# Resolver.net
KiCad netlist of a schematic drawn in Altium Designer
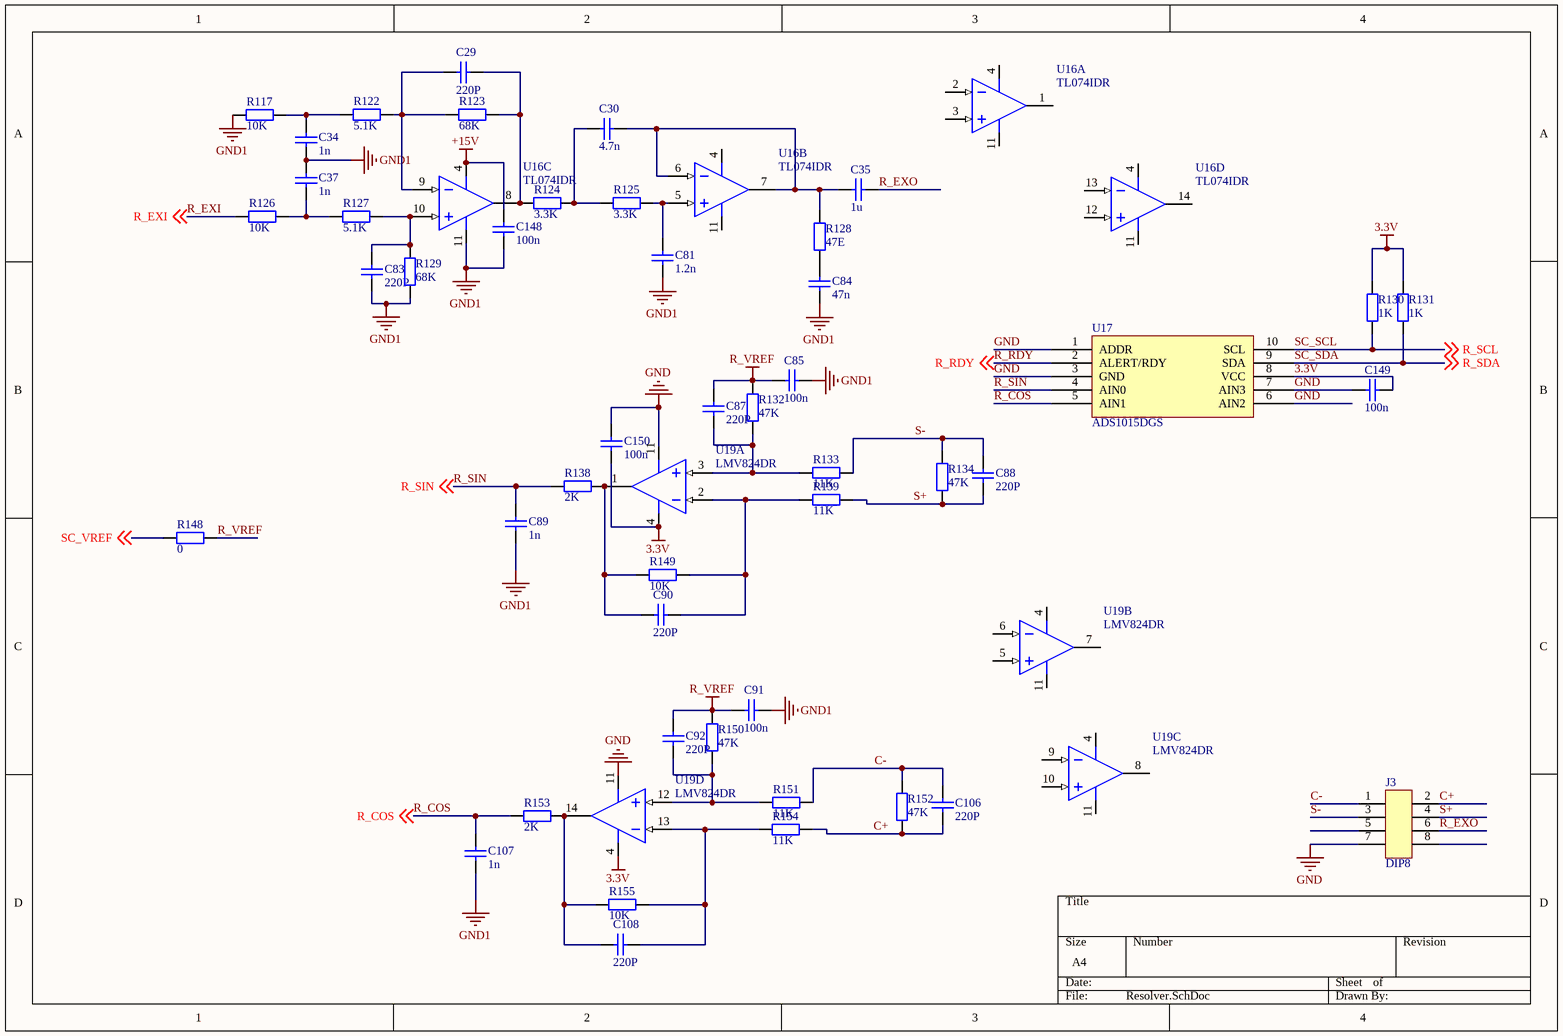
[diagram p0: Resolver.SchDoc]

(export (version "E")
  (design (tool "Eeschema 10.0.6"))
  (components
    (comp (ref "C29")
      (value "220P")
      (footprint "0603C")
      (description "Capacitor")
      (fields (field (name "PUBLISHER") "Altium Limited"))
      (libsource (lib "Main_C") (part "Cap"))
    )
    (comp (ref "C30")
      (value "4.7n")
      (footprint "0603C")
      (description "Capacitor")
      (fields (field (name "PUBLISHER") "Altium Limited"))
      (libsource (lib "Main_C") (part "Cap"))
    )
    (comp (ref "C34")
      (value "1n")
      (footprint "0603C")
      (description "Capacitor")
      (fields (field (name "PUBLISHER") "Altium Limited"))
      (libsource (lib "Main_C") (part "Cap"))
    )
    (comp (ref "C35")
      (value "1u")
      (footprint "0603C")
      (description "Capacitor")
      (fields (field (name "PUBLISHER") "Altium Limited"))
      (libsource (lib "Main_C") (part "Cap"))
    )
    (comp (ref "C37")
      (value "1n")
      (footprint "0603C")
      (description "Capacitor")
      (fields (field (name "PUBLISHER") "Altium Limited"))
      (libsource (lib "Main_C") (part "Cap"))
    )
    (comp (ref "C81")
      (value "1.2n")
      (footprint "0603C")
      (description "Capacitor")
      (fields (field (name "PUBLISHER") "Altium Limited"))
      (libsource (lib "Main_C") (part "Cap"))
    )
    (comp (ref "C83")
      (value "220P")
      (footprint "0603C")
      (description "Capacitor")
      (fields (field (name "PUBLISHER") "Altium Limited"))
      (libsource (lib "Main_C") (part "Cap"))
    )
    (comp (ref "C84")
      (value "47n")
      (footprint "0603C")
      (description "Capacitor")
      (fields (field (name "PUBLISHER") "Altium Limited"))
      (libsource (lib "Main_C") (part "Cap"))
    )
    (comp (ref "C85")
      (value "100n")
      (footprint "0603C")
      (description "Capacitor")
      (fields (field (name "PUBLISHER") "Altium Limited"))
      (libsource (lib "Main_C") (part "Cap"))
    )
    (comp (ref "C87")
      (value "220P")
      (footprint "0603C")
      (description "Capacitor")
      (fields (field (name "PUBLISHER") "Altium Limited"))
      (libsource (lib "Main_C") (part "Cap"))
    )
    (comp (ref "C88")
      (value "220P")
      (footprint "0603C")
      (description "Capacitor")
      (fields (field (name "PUBLISHER") "Altium Limited"))
      (libsource (lib "Main_C") (part "Cap"))
    )
    (comp (ref "C89")
      (value "1n")
      (footprint "0603C")
      (description "Capacitor")
      (fields (field (name "PUBLISHER") "Altium Limited"))
      (libsource (lib "Main_C") (part "Cap"))
    )
    (comp (ref "C90")
      (value "220P")
      (footprint "0603C")
      (description "Capacitor")
      (fields (field (name "PUBLISHER") "Altium Limited"))
      (libsource (lib "Main_C") (part "Cap"))
    )
    (comp (ref "C91")
      (value "100n")
      (footprint "0603C")
      (description "Capacitor")
      (fields (field (name "PUBLISHER") "Altium Limited"))
      (libsource (lib "Main_C") (part "Cap"))
    )
    (comp (ref "C92")
      (value "220P")
      (footprint "0603C")
      (description "Capacitor")
      (fields (field (name "PUBLISHER") "Altium Limited"))
      (libsource (lib "Main_C") (part "Cap"))
    )
    (comp (ref "C106")
      (value "220P")
      (footprint "0603C")
      (description "Capacitor")
      (fields (field (name "PUBLISHER") "Altium Limited"))
      (libsource (lib "Main_C") (part "Cap"))
    )
    (comp (ref "C107")
      (value "1n")
      (footprint "0603C")
      (description "Capacitor")
      (fields (field (name "PUBLISHER") "Altium Limited"))
      (libsource (lib "Main_C") (part "Cap"))
    )
    (comp (ref "C108")
      (value "220P")
      (footprint "0603C")
      (description "Capacitor")
      (fields (field (name "PUBLISHER") "Altium Limited"))
      (libsource (lib "Main_C") (part "Cap"))
    )
    (comp (ref "C148")
      (value "100n")
      (footprint "0603C")
      (description "Capacitor")
      (fields (field (name "PUBLISHER") "Altium Limited"))
      (libsource (lib "Main_C") (part "Cap"))
    )
    (comp (ref "C149")
      (value "100n")
      (footprint "0603C")
      (description "Capacitor")
      (fields (field (name "PUBLISHER") "Altium Limited"))
      (libsource (lib "Main_C") (part "Cap"))
    )
    (comp (ref "C150")
      (value "100n")
      (footprint "0603C")
      (description "Capacitor")
      (fields (field (name "PUBLISHER") "Altium Limited"))
      (libsource (lib "Main_C") (part "Cap"))
    )
    (comp (ref "J3")
      (value "DIP8")
      (footprint "DIP8-2.54")
      (description "Connectors")
      (fields (field (name "PUBLISHER") "Altium Limited"))
      (libsource (lib "jointbar") (part "DIP8"))
    )
    (comp (ref "R117")
      (value "10K")
      (footprint "0603R")
      (description "Resistor")
      (fields (field (name "PUBLISHER") "Altium Limited"))
      (libsource (lib "") (part "Res2_1"))
    )
    (comp (ref "R122")
      (value "5.1K")
      (footprint "0603R")
      (description "Resistor")
      (fields (field (name "PUBLISHER") "Altium Limited"))
      (libsource (lib "") (part "Res2_1"))
    )
    (comp (ref "R123")
      (value "68K")
      (footprint "0603R")
      (description "Resistor")
      (fields (field (name "PUBLISHER") "Altium Limited"))
      (libsource (lib "") (part "Res2_1"))
    )
    (comp (ref "R124")
      (value "3.3K")
      (footprint "0603R")
      (description "Resistor")
      (fields (field (name "PUBLISHER") "Altium Limited"))
      (libsource (lib "") (part "Res2_1"))
    )
    (comp (ref "R125")
      (value "3.3K")
      (footprint "0603R")
      (description "Resistor")
      (fields (field (name "PUBLISHER") "Altium Limited"))
      (libsource (lib "") (part "Res2_1"))
    )
    (comp (ref "R126")
      (value "10K")
      (footprint "0603R")
      (description "Resistor")
      (fields (field (name "PUBLISHER") "Altium Limited"))
      (libsource (lib "") (part "Res2_1"))
    )
    (comp (ref "R127")
      (value "5.1K")
      (footprint "0603R")
      (description "Resistor")
      (fields (field (name "PUBLISHER") "Altium Limited"))
      (libsource (lib "") (part "Res2_1"))
    )
    (comp (ref "R128")
      (value "47E")
      (footprint "0603R")
      (description "Resistor")
      (fields (field (name "PUBLISHER") "Altium Limited"))
      (libsource (lib "Main_C") (part "Res2"))
    )
    (comp (ref "R129")
      (value "68K")
      (footprint "0603R")
      (description "Resistor")
      (fields (field (name "PUBLISHER") "Altium Limited"))
      (libsource (lib "Main_C") (part "Res2"))
    )
    (comp (ref "R130")
      (value "1K")
      (footprint "0603R")
      (description "Resistor")
      (fields (field (name "PUBLISHER") "Altium Limited"))
      (libsource (lib "Main_C") (part "Res2"))
    )
    (comp (ref "R131")
      (value "1K")
      (footprint "0603R")
      (description "Resistor")
      (fields (field (name "PUBLISHER") "Altium Limited"))
      (libsource (lib "Main_C") (part "Res2"))
    )
    (comp (ref "R132")
      (value "47K")
      (footprint "0603R")
      (description "Resistor")
      (fields (field (name "PUBLISHER") "Altium Limited"))
      (libsource (lib "Main_C") (part "Res2"))
    )
    (comp (ref "R133")
      (value "11K")
      (footprint "0603R")
      (description "Resistor")
      (fields (field (name "PUBLISHER") "Altium Limited"))
      (libsource (lib "") (part "Res2_1"))
    )
    (comp (ref "R134")
      (value "47K")
      (footprint "0603R")
      (description "Resistor")
      (fields (field (name "PUBLISHER") "Altium Limited"))
      (libsource (lib "Main_C") (part "Res2"))
    )
    (comp (ref "R138")
      (value "2K")
      (footprint "0603R")
      (description "Resistor")
      (fields (field (name "PUBLISHER") "Altium Limited"))
      (libsource (lib "") (part "Res2_2"))
    )
    (comp (ref "R139")
      (value "11K")
      (footprint "0603R")
      (description "Resistor")
      (fields (field (name "PUBLISHER") "Altium Limited"))
      (libsource (lib "") (part "Res2_1"))
    )
    (comp (ref "R148")
      (value "0")
      (footprint "0603R")
      (description "Resistor")
      (fields (field (name "PUBLISHER") "Altium Limited"))
      (libsource (lib "") (part "Res2_1"))
    )
    (comp (ref "R149")
      (value "10K")
      (footprint "0603R")
      (description "Resistor")
      (fields (field (name "PUBLISHER") "Altium Limited"))
      (libsource (lib "") (part "Res2_2"))
    )
    (comp (ref "R150")
      (value "47K")
      (footprint "0603R")
      (description "Resistor")
      (fields (field (name "PUBLISHER") "Altium Limited"))
      (libsource (lib "Main_C") (part "Res2"))
    )
    (comp (ref "R151")
      (value "11K")
      (footprint "0603R")
      (description "Resistor")
      (fields (field (name "PUBLISHER") "Altium Limited"))
      (libsource (lib "") (part "Res2_1"))
    )
    (comp (ref "R152")
      (value "47K")
      (footprint "0603R")
      (description "Resistor")
      (fields (field (name "PUBLISHER") "Altium Limited"))
      (libsource (lib "Main_C") (part "Res2"))
    )
    (comp (ref "R153")
      (value "2K")
      (footprint "0603R")
      (description "Resistor")
      (fields (field (name "PUBLISHER") "Altium Limited"))
      (libsource (lib "") (part "Res2_2"))
    )
    (comp (ref "R154")
      (value "11K")
      (footprint "0603R")
      (description "Resistor")
      (fields (field (name "PUBLISHER") "Altium Limited"))
      (libsource (lib "") (part "Res2_1"))
    )
    (comp (ref "R155")
      (value "10K")
      (footprint "0603R")
      (description "Resistor")
      (fields (field (name "PUBLISHER") "Altium Limited"))
      (libsource (lib "") (part "Res2_2"))
    )
    (comp (ref "U16")
      (value "TL074IDR")
      (footprint "SOP-14")
      (description "Quad Single-Supply Comparator")
      (fields (field (name "PUBLISHER") "Altium Limited"))
      (libsource (lib "Main_C") (part "LM339AD"))
    )
    (comp (ref "U17") (value "ADS1015DGS") (footprint "VSSOP-10") (libsource (lib "Main_C") (part "ADS1015")))
    (comp (ref "U19")
      (value "LMV824DR")
      (footprint "SOP-14")
      (description "Quad Single-Supply Comparator")
      (fields (field (name "PUBLISHER") "Altium Limited"))
      (libsource (lib "Main_C") (part "LM339AD"))
    )
  )
  (nets
    (net (code "1") (name "+15V") (class "Default")
      (node (ref "C148") (pin "2") (pinfunction "2_2") (pintype "passive"))
      (node (ref "U16") (pin "4") (pinfunction "GND_4") (pintype "power_in"))
    )
    (net (code "2") (name "/C+") (class "Default")
      (node (ref "C106") (pin "2") (pinfunction "2_2") (pintype "passive"))
      (node (ref "J3") (pin "2") (pinfunction "2_2") (pintype "passive"))
      (node (ref "R152") (pin "2") (pinfunction "2_2") (pintype "passive"))
      (node (ref "R154") (pin "1") (pinfunction "1_1") (pintype "passive"))
    )
    (net (code "3") (name "/C-") (class "Default")
      (node (ref "C106") (pin "1") (pinfunction "1_1") (pintype "passive"))
      (node (ref "J3") (pin "1") (pinfunction "1_1") (pintype "passive"))
      (node (ref "R151") (pin "1") (pinfunction "1_1") (pintype "passive"))
      (node (ref "R152") (pin "1") (pinfunction "1_1") (pintype "passive"))
    )
    (net (code "4") (name "/R_EXO") (class "Default")
      (node (ref "C35") (pin "2") (pinfunction "2_2") (pintype "passive"))
      (node (ref "J3") (pin "6") (pinfunction "6_6") (pintype "passive"))
    )
    (net (code "5") (name "/S+") (class "Default")
      (node (ref "C88") (pin "2") (pinfunction "2_2") (pintype "passive"))
      (node (ref "J3") (pin "4") (pinfunction "4_4") (pintype "passive"))
      (node (ref "R134") (pin "2") (pinfunction "2_2") (pintype "passive"))
      (node (ref "R139") (pin "1") (pinfunction "1_1") (pintype "passive"))
    )
    (net (code "6") (name "/S-") (class "Default")
      (node (ref "C88") (pin "1") (pinfunction "1_1") (pintype "passive"))
      (node (ref "J3") (pin "3") (pinfunction "3_3") (pintype "passive"))
      (node (ref "R133") (pin "1") (pinfunction "1_1") (pintype "passive"))
      (node (ref "R134") (pin "1") (pinfunction "1_1") (pintype "passive"))
    )
    (net (code "7") (name "3.3V") (class "Default")
      (node (ref "C149") (pin "2") (pinfunction "2_2") (pintype "passive"))
      (node (ref "C150") (pin "1") (pinfunction "1_1") (pintype "passive"))
      (node (ref "R130") (pin "1") (pinfunction "1_1") (pintype "passive"))
      (node (ref "R131") (pin "1") (pinfunction "1_1") (pintype "passive"))
      (node (ref "U17") (pin "8") (pinfunction "VCC_8") (pintype "passive"))
      (node (ref "U19") (pin "4") (pinfunction "GND_4") (pintype "power_in"))
    )
    (net (code "8") (name "GND") (class "Default")
      (node (ref "C149") (pin "1") (pinfunction "1_1") (pintype "passive"))
      (node (ref "C150") (pin "2") (pinfunction "2_2") (pintype "passive"))
      (node (ref "J3") (pin "7") (pinfunction "7_7") (pintype "passive"))
      (node (ref "U17") (pin "1") (pinfunction "ADDR_1") (pintype "passive"))
      (node (ref "U17") (pin "3") (pinfunction "GND_3") (pintype "passive"))
      (node (ref "U17") (pin "6") (pinfunction "AIN2_6") (pintype "passive"))
      (node (ref "U17") (pin "7") (pinfunction "AIN3_7") (pintype "passive"))
      (node (ref "U19") (pin "11") (pinfunction "V+_11") (pintype "power_in"))
    )
    (net (code "9") (name "GND1") (class "Default")
      (node (ref "C107") (pin "1") (pinfunction "1_1") (pintype "passive"))
      (node (ref "C148") (pin "1") (pinfunction "1_1") (pintype "passive"))
      (node (ref "C34") (pin "1") (pinfunction "1_1") (pintype "passive"))
      (node (ref "C37") (pin "2") (pinfunction "2_2") (pintype "passive"))
      (node (ref "C81") (pin "1") (pinfunction "1_1") (pintype "passive"))
      (node (ref "C83") (pin "1") (pinfunction "1_1") (pintype "passive"))
      (node (ref "C84") (pin "1") (pinfunction "1_1") (pintype "passive"))
      (node (ref "C85") (pin "1") (pinfunction "1_1") (pintype "passive"))
      (node (ref "C89") (pin "1") (pinfunction "1_1") (pintype "passive"))
      (node (ref "C91") (pin "1") (pinfunction "1_1") (pintype "passive"))
      (node (ref "R117") (pin "2") (pinfunction "2_2") (pintype "passive"))
      (node (ref "R129") (pin "2") (pinfunction "2_2") (pintype "passive"))
      (node (ref "U16") (pin "11") (pinfunction "V+_11") (pintype "power_in"))
    )
    (net (code "10") (name "Net-(C30-Pad1)") (class "Default")
      (node (ref "C30") (pin "1") (pinfunction "1_1") (pintype "passive"))
      (node (ref "R124") (pin "1") (pinfunction "1_1") (pintype "passive"))
      (node (ref "R125") (pin "2") (pinfunction "2_2") (pintype "passive"))
    )
    (net (code "11") (name "Net-(C34-Pad2)") (class "Default")
      (node (ref "C34") (pin "2") (pinfunction "2_2") (pintype "passive"))
      (node (ref "R117") (pin "1") (pinfunction "1_1") (pintype "passive"))
      (node (ref "R122") (pin "2") (pinfunction "2_2") (pintype "passive"))
    )
    (net (code "12") (name "Net-(C37-Pad1)") (class "Default")
      (node (ref "C37") (pin "1") (pinfunction "1_1") (pintype "passive"))
      (node (ref "R126") (pin "1") (pinfunction "1_1") (pintype "passive"))
      (node (ref "R127") (pin "2") (pinfunction "2_2") (pintype "passive"))
    )
    (net (code "13") (name "Net-(C84-Pad2)") (class "Default")
      (node (ref "C84") (pin "2") (pinfunction "2_2") (pintype "passive"))
      (node (ref "R128") (pin "2") (pinfunction "2_2") (pintype "passive"))
    )
    (net (code "14") (name "Net-(U16B-IN+)") (class "Default")
      (node (ref "C81") (pin "2") (pinfunction "2_2") (pintype "passive"))
      (node (ref "R125") (pin "1") (pinfunction "1_1") (pintype "passive"))
      (node (ref "U16") (pin "5") (pinfunction "IN+_5") (pintype "input"))
    )
    (net (code "15") (name "Net-(U16B-IN-)") (class "Default")
      (node (ref "C30") (pin "2") (pinfunction "2_2") (pintype "passive"))
      (node (ref "C35") (pin "1") (pinfunction "1_1") (pintype "passive"))
      (node (ref "R128") (pin "1") (pinfunction "1_1") (pintype "passive"))
      (node (ref "U16") (pin "6") (pinfunction "IN-_6") (pintype "input"))
      (node (ref "U16") (pin "7") (pinfunction "OUT2_7") (pintype "open_collector"))
    )
    (net (code "16") (name "Net-(U16C-IN+)") (class "Default")
      (node (ref "C83") (pin "2") (pinfunction "2_2") (pintype "passive"))
      (node (ref "R127") (pin "1") (pinfunction "1_1") (pintype "passive"))
      (node (ref "R129") (pin "1") (pinfunction "1_1") (pintype "passive"))
      (node (ref "U16") (pin "10") (pinfunction "IN+_10") (pintype "input"))
    )
    (net (code "17") (name "Net-(U16C-IN-)") (class "Default")
      (node (ref "C29") (pin "1") (pinfunction "1_1") (pintype "passive"))
      (node (ref "R122") (pin "1") (pinfunction "1_1") (pintype "passive"))
      (node (ref "R123") (pin "2") (pinfunction "2_2") (pintype "passive"))
      (node (ref "U16") (pin "9") (pinfunction "IN-_9") (pintype "input"))
    )
    (net (code "18") (name "Net-(U16C-OUT)") (class "Default")
      (node (ref "C29") (pin "2") (pinfunction "2_2") (pintype "passive"))
      (node (ref "R123") (pin "1") (pinfunction "1_1") (pintype "passive"))
      (node (ref "R124") (pin "2") (pinfunction "2_2") (pintype "passive"))
      (node (ref "U16") (pin "8") (pinfunction "OUT_8") (pintype "open_collector"))
    )
    (net (code "19") (name "Net-(U19A-IN+)") (class "Default")
      (node (ref "C87") (pin "1") (pinfunction "1_1") (pintype "passive"))
      (node (ref "R132") (pin "2") (pinfunction "2_2") (pintype "passive"))
      (node (ref "R133") (pin "2") (pinfunction "2_2") (pintype "passive"))
      (node (ref "U19") (pin "3") (pinfunction "IN+_3") (pintype "input"))
    )
    (net (code "20") (name "Net-(U19A-IN-)") (class "Default")
      (node (ref "C90") (pin "2") (pinfunction "2_2") (pintype "passive"))
      (node (ref "R139") (pin "2") (pinfunction "2_2") (pintype "passive"))
      (node (ref "R149") (pin "2") (pinfunction "2_2") (pintype "passive"))
      (node (ref "U19") (pin "2") (pinfunction "IN-_2") (pintype "input"))
    )
    (net (code "21") (name "Net-(U19A-OUT)") (class "Default")
      (node (ref "C90") (pin "1") (pinfunction "1_1") (pintype "passive"))
      (node (ref "R138") (pin "2") (pinfunction "2_2") (pintype "passive"))
      (node (ref "R149") (pin "1") (pinfunction "1_1") (pintype "passive"))
      (node (ref "U19") (pin "1") (pinfunction "OUT_1") (pintype "open_collector"))
    )
    (net (code "22") (name "Net-(U19D-IN+)") (class "Default")
      (node (ref "C92") (pin "1") (pinfunction "1_1") (pintype "passive"))
      (node (ref "R150") (pin "2") (pinfunction "2_2") (pintype "passive"))
      (node (ref "R151") (pin "2") (pinfunction "2_2") (pintype "passive"))
      (node (ref "U19") (pin "12") (pinfunction "IN+_12") (pintype "input"))
    )
    (net (code "23") (name "Net-(U19D-IN-)") (class "Default")
      (node (ref "C108") (pin "2") (pinfunction "2_2") (pintype "passive"))
      (node (ref "R154") (pin "2") (pinfunction "2_2") (pintype "passive"))
      (node (ref "R155") (pin "2") (pinfunction "2_2") (pintype "passive"))
      (node (ref "U19") (pin "13") (pinfunction "IN-_13") (pintype "input"))
    )
    (net (code "24") (name "Net-(U19D-OUT)") (class "Default")
      (node (ref "C108") (pin "1") (pinfunction "1_1") (pintype "passive"))
      (node (ref "R153") (pin "2") (pinfunction "2_2") (pintype "passive"))
      (node (ref "R155") (pin "1") (pinfunction "1_1") (pintype "passive"))
      (node (ref "U19") (pin "14") (pinfunction "OUT_14") (pintype "open_collector"))
    )
    (net (code "25") (name "R_COS") (class "Default")
      (node (ref "C107") (pin "2") (pinfunction "2_2") (pintype "passive"))
      (node (ref "R153") (pin "1") (pinfunction "1_1") (pintype "passive"))
      (node (ref "U17") (pin "5") (pinfunction "AIN1_5") (pintype "passive"))
    )
    (net (code "26") (name "R_EXI") (class "Default")
      (node (ref "R126") (pin "2") (pinfunction "2_2") (pintype "passive"))
    )
    (net (code "27") (name "R_RDY") (class "Default")
      (node (ref "U17") (pin "2") (pinfunction "ALERT/RDY_2") (pintype "passive"))
    )
    (net (code "28") (name "R_SCL") (class "Default")
      (node (ref "R130") (pin "2") (pinfunction "2_2") (pintype "passive"))
      (node (ref "U17") (pin "10") (pinfunction "SCL_10") (pintype "passive"))
    )
    (net (code "29") (name "R_SDA") (class "Default")
      (node (ref "R131") (pin "2") (pinfunction "2_2") (pintype "passive"))
      (node (ref "U17") (pin "9") (pinfunction "SDA_9") (pintype "passive"))
    )
    (net (code "30") (name "R_SIN") (class "Default")
      (node (ref "C89") (pin "2") (pinfunction "2_2") (pintype "passive"))
      (node (ref "R138") (pin "1") (pinfunction "1_1") (pintype "passive"))
      (node (ref "U17") (pin "4") (pinfunction "AIN0_4") (pintype "passive"))
    )
    (net (code "31") (name "R_VREF") (class "Default")
      (node (ref "C85") (pin "2") (pinfunction "2_2") (pintype "passive"))
      (node (ref "C87") (pin "2") (pinfunction "2_2") (pintype "passive"))
      (node (ref "C91") (pin "2") (pinfunction "2_2") (pintype "passive"))
      (node (ref "C92") (pin "2") (pinfunction "2_2") (pintype "passive"))
      (node (ref "R132") (pin "1") (pinfunction "1_1") (pintype "passive"))
      (node (ref "R148") (pin "1") (pinfunction "1_1") (pintype "passive"))
      (node (ref "R150") (pin "1") (pinfunction "1_1") (pintype "passive"))
    )
    (net (code "32") (name "SC_VREF") (class "Default")
      (node (ref "R148") (pin "2") (pinfunction "2_2") (pintype "passive"))
    )
    (net (code "33") (name "unconnected-(J3-Pad5)") (class "Default")
      (node (ref "J3") (pin "5") (pinfunction "5_5") (pintype "passive"))
    )
    (net (code "34") (name "unconnected-(J3-Pad8)") (class "Default")
      (node (ref "J3") (pin "8") (pinfunction "8_8") (pintype "passive"))
    )
    (net (code "35") (name "unconnected-(U16A-GND-Pad4)") (class "Default")
      (node (ref "U16") (pin "4") (pinfunction "GND_4") (pintype "power_in"))
    )
    (net (code "36") (name "unconnected-(U16A-IN+-Pad3)") (class "Default")
      (node (ref "U16") (pin "3") (pinfunction "IN+_3") (pintype "input"))
    )
    (net (code "37") (name "unconnected-(U16A-IN--Pad2)") (class "Default")
      (node (ref "U16") (pin "2") (pinfunction "IN-_2") (pintype "input"))
    )
    (net (code "38") (name "unconnected-(U16A-OUT-Pad1)") (class "Default")
      (node (ref "U16") (pin "1") (pinfunction "OUT_1") (pintype "open_collector"))
    )
    (net (code "39") (name "unconnected-(U16A-V+-Pad11)") (class "Default")
      (node (ref "U16") (pin "11") (pinfunction "V+_11") (pintype "power_in"))
    )
    (net (code "40") (name "unconnected-(U16B-GND-Pad4)") (class "Default")
      (node (ref "U16") (pin "4") (pinfunction "GND_4") (pintype "power_in"))
    )
    (net (code "41") (name "unconnected-(U16B-V+-Pad11)") (class "Default")
      (node (ref "U16") (pin "11") (pinfunction "V+_11") (pintype "power_in"))
    )
    (net (code "42") (name "unconnected-(U16D-GND-Pad4)") (class "Default")
      (node (ref "U16") (pin "4") (pinfunction "GND_4") (pintype "power_in"))
    )
    (net (code "43") (name "unconnected-(U16D-IN+-Pad12)") (class "Default")
      (node (ref "U16") (pin "12") (pinfunction "IN+_12") (pintype "input"))
    )
    (net (code "44") (name "unconnected-(U16D-IN--Pad13)") (class "Default")
      (node (ref "U16") (pin "13") (pinfunction "IN-_13") (pintype "input"))
    )
    (net (code "45") (name "unconnected-(U16D-OUT-Pad14)") (class "Default")
      (node (ref "U16") (pin "14") (pinfunction "OUT_14") (pintype "open_collector"))
    )
    (net (code "46") (name "unconnected-(U16D-V+-Pad11)") (class "Default")
      (node (ref "U16") (pin "11") (pinfunction "V+_11") (pintype "power_in"))
    )
    (net (code "47") (name "unconnected-(U19B-GND-Pad4)") (class "Default")
      (node (ref "U19") (pin "4") (pinfunction "GND_4") (pintype "power_in"))
    )
    (net (code "48") (name "unconnected-(U19B-IN+-Pad5)") (class "Default")
      (node (ref "U19") (pin "5") (pinfunction "IN+_5") (pintype "input"))
    )
    (net (code "49") (name "unconnected-(U19B-IN--Pad6)") (class "Default")
      (node (ref "U19") (pin "6") (pinfunction "IN-_6") (pintype "input"))
    )
    (net (code "50") (name "unconnected-(U19B-OUT2-Pad7)") (class "Default")
      (node (ref "U19") (pin "7") (pinfunction "OUT2_7") (pintype "open_collector"))
    )
    (net (code "51") (name "unconnected-(U19B-V+-Pad11)") (class "Default")
      (node (ref "U19") (pin "11") (pinfunction "V+_11") (pintype "power_in"))
    )
    (net (code "52") (name "unconnected-(U19C-GND-Pad4)") (class "Default")
      (node (ref "U19") (pin "4") (pinfunction "GND_4") (pintype "power_in"))
    )
    (net (code "53") (name "unconnected-(U19C-IN+-Pad10)") (class "Default")
      (node (ref "U19") (pin "10") (pinfunction "IN+_10") (pintype "input"))
    )
    (net (code "54") (name "unconnected-(U19C-IN--Pad9)") (class "Default")
      (node (ref "U19") (pin "9") (pinfunction "IN-_9") (pintype "input"))
    )
    (net (code "55") (name "unconnected-(U19C-OUT-Pad8)") (class "Default")
      (node (ref "U19") (pin "8") (pinfunction "OUT_8") (pintype "open_collector"))
    )
    (net (code "56") (name "unconnected-(U19C-V+-Pad11)") (class "Default")
      (node (ref "U19") (pin "11") (pinfunction "V+_11") (pintype "power_in"))
    )
  )
)
